# 1-Schematic_CnE_Project_PCB.net
KiCad netlist of a schematic drawn in EasyEDA
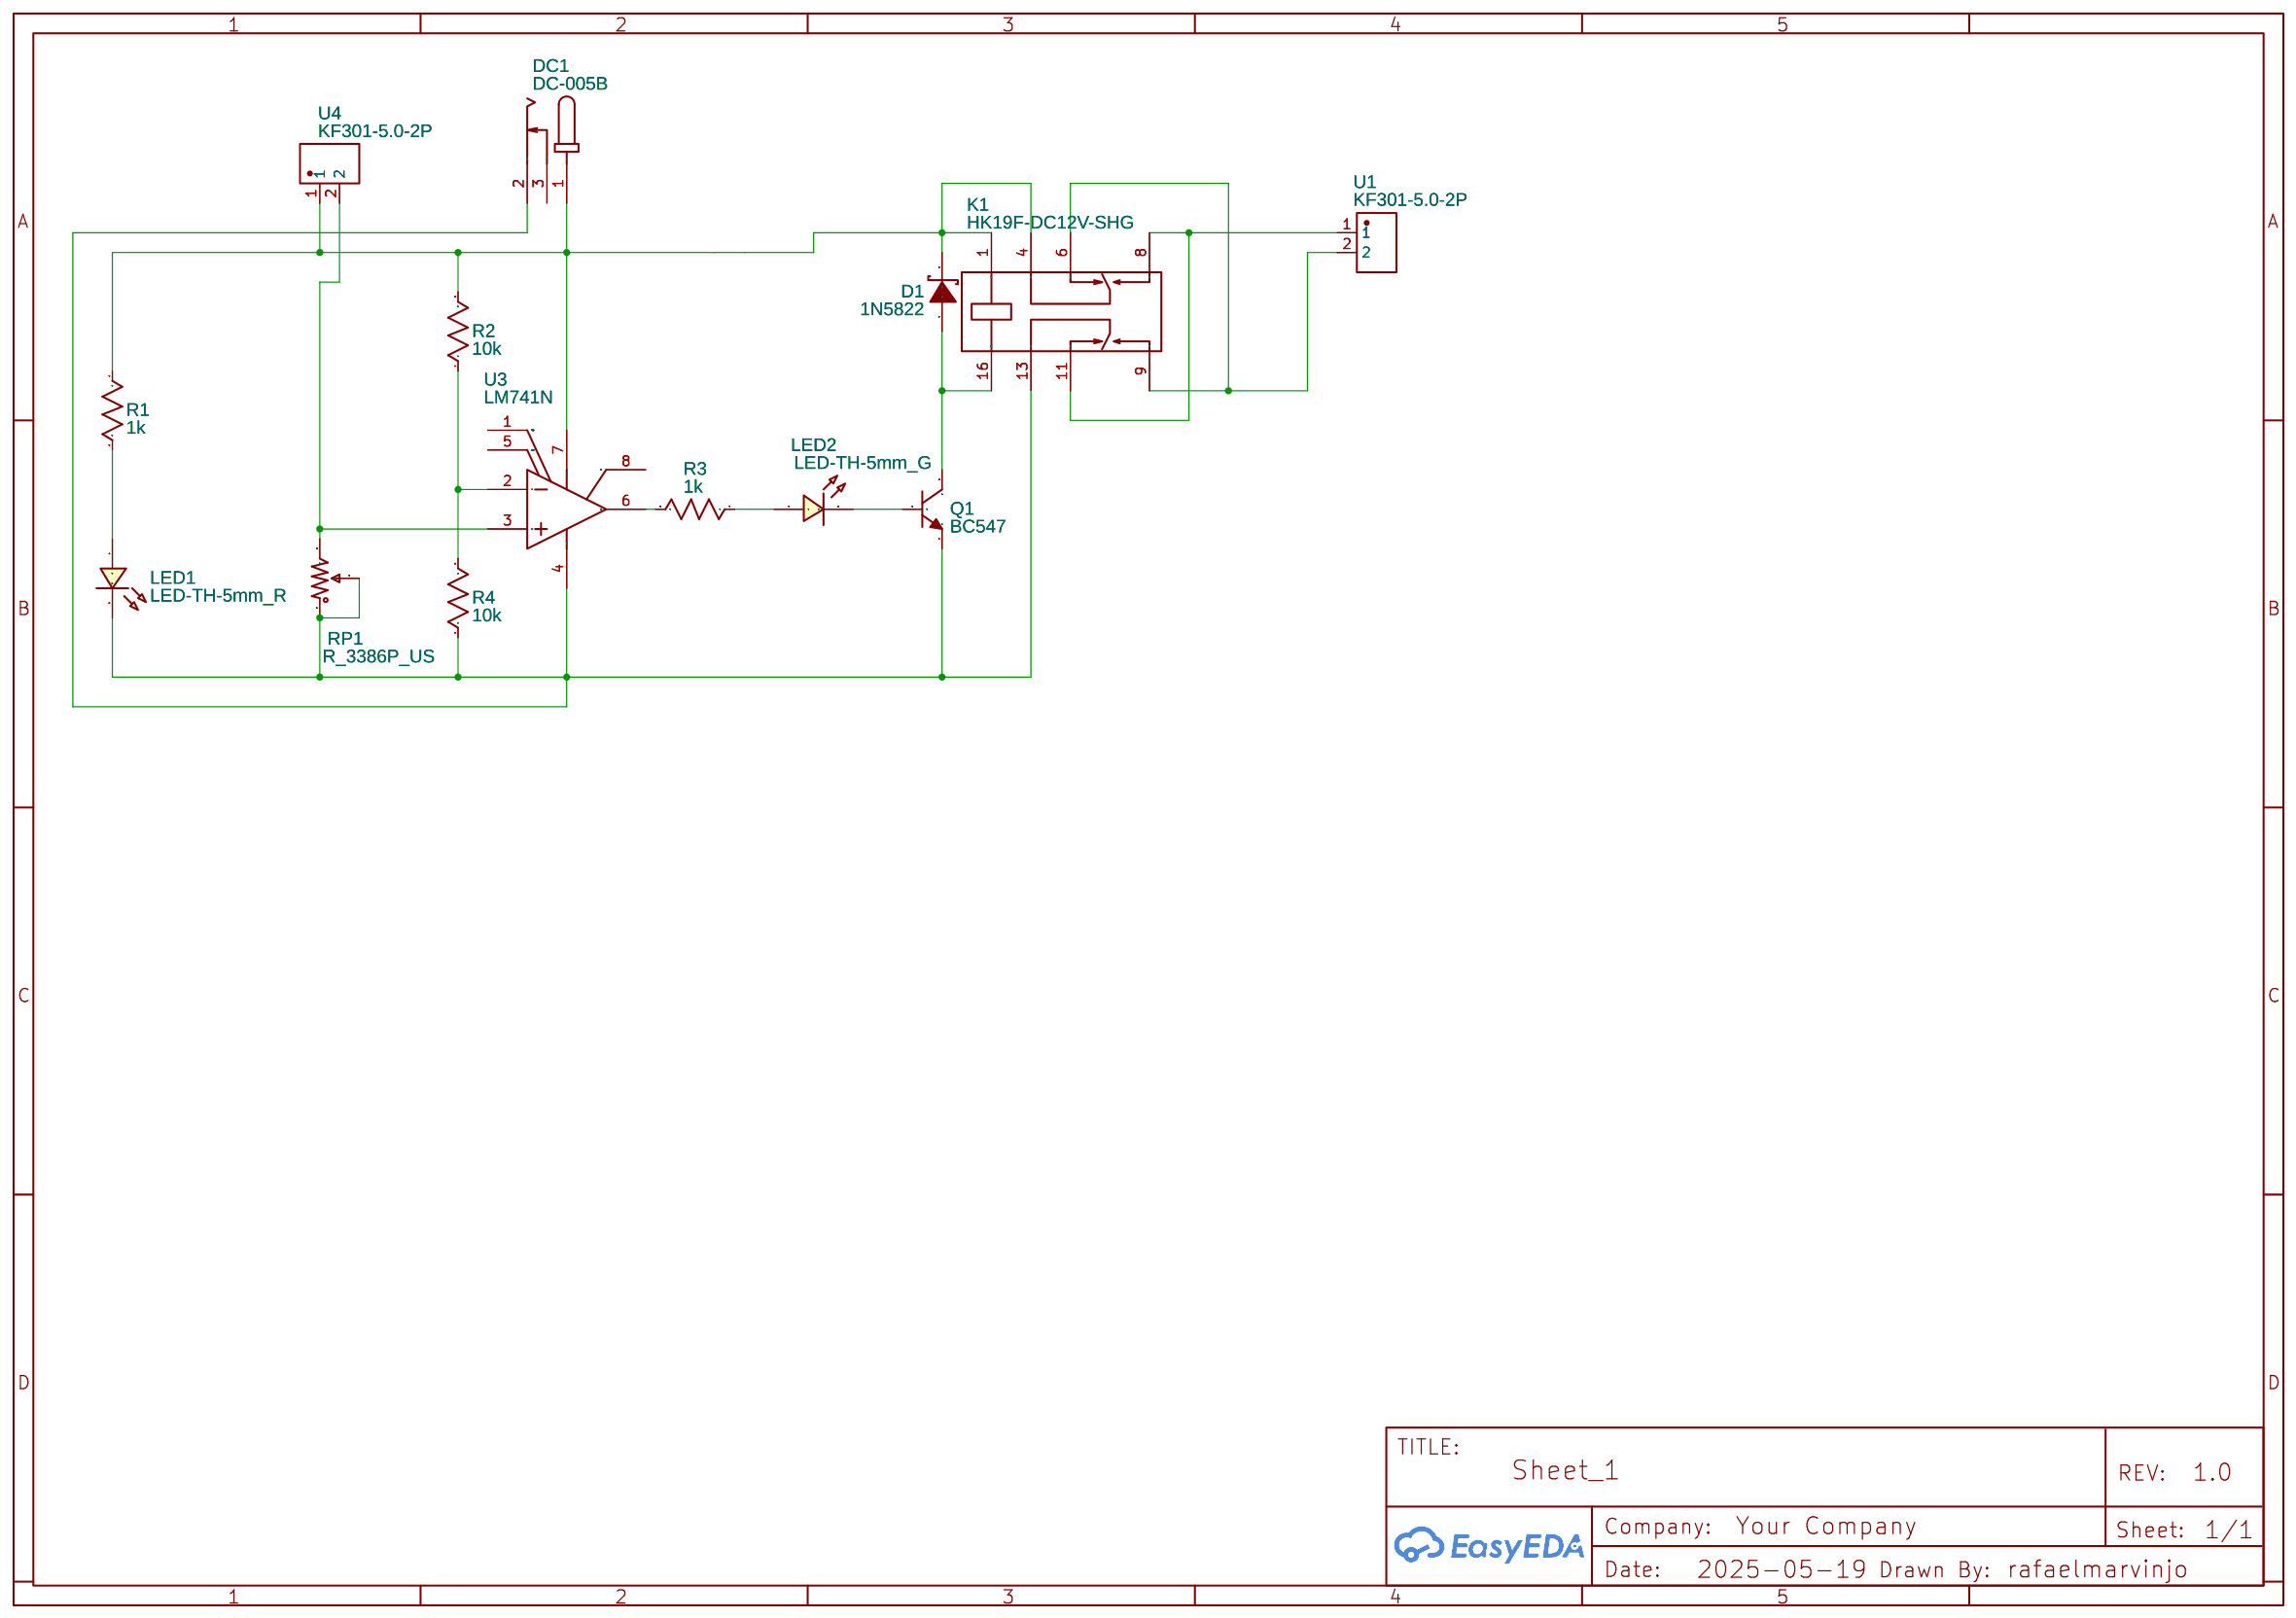
[diagram p0: schematic sheet]

(export (version "E")
  (design (tool "Eeschema 10.0.6"))
  (components
    (comp (ref "D1")
      (value "1N5822")
      (fields (field (name "Manufacturer") "MDD(辰达半导体)"))
      (libsource (lib "") (part "1N5822"))
    )
    (comp (ref "DC1") (value "DC-005B") (libsource (lib "") (part "DC-005B")))
    (comp (ref "K1")
      (value "HK19F-DC12V-SHG")
      (fields (field (name "Manufacturer") "汇科"))
      (libsource (lib "") (part "HK19F-DC12V-SHG"))
    )
    (comp (ref "LED1")
      (value "LED-TH-5mm_R")
      (fields
        (field (name "Manufacturer Part") "333-2SURD/S530-A3")
        (field (name "Manufacturer") "EVERLIGHT(台湾亿光)")
      )
      (libsource (lib "") (part "LED-TH-5mm_R"))
    )
    (comp (ref "LED2")
      (value "LED-TH-5mm_G")
      (fields
        (field (name "Manufacturer Part") "333-2SYGD/S530-E2")
        (field (name "Manufacturer") "EVERLIGHT(台湾亿光)")
      )
      (libsource (lib "") (part "LED-TH-5mm_G"))
    )
    (comp (ref "Q1")
      (value "BC547")
      (fields (field (name "Manufacturer Part") "2N3904") (field (name "Manufacturer") "SEMTECH"))
      (libsource (lib "") (part "2N3904(TO-92)"))
    )
    (comp (ref "R1") (value "1k") (libsource (lib "") (part "R_AXIAL-0.3_US_2")))
    (comp (ref "R2") (value "10k") (libsource (lib "") (part "R_AXIAL-0.3_US_1")))
    (comp (ref "R3") (value "1k") (libsource (lib "") (part "R_AXIAL-0.3_US")))
    (comp (ref "R4") (value "10k") (libsource (lib "") (part "R_AXIAL-0.3_US_1")))
    (comp (ref "RP1") (value "R_3386P_US") (libsource (lib "") (part "R_3386P_US")))
    (comp (ref "U1")
      (value "KF301-5.0-2P")
      (fields (field (name "Manufacturer") "KEFA(科发)"))
      (libsource (lib "") (part "KF301-5.0-2P"))
    )
    (comp (ref "U3")
      (value "LM741N")
      (fields (field (name "Manufacturer") "HGSEMI(华冠)"))
      (libsource (lib "") (part "LM741N"))
    )
    (comp (ref "U4")
      (value "KF301-5.0-2P")
      (fields (field (name "Manufacturer") "KEFA(科发)"))
      (libsource (lib "") (part "KF301-5.0-2P_1"))
    )
  )
  (nets
    (net (code "1") (name "Net-(D1-A)") (class "Default")
      (node (ref "D1") (pin "1") (pinfunction "A_1") (pintype "unspecified"))
      (node (ref "K1") (pin "16") (pinfunction "16_16") (pintype "unspecified"))
      (node (ref "Q1") (pin "3") (pinfunction "C_3") (pintype "unspecified"))
    )
    (net (code "2") (name "Net-(D1-K)") (class "Default")
      (node (ref "D1") (pin "2") (pinfunction "K_2") (pintype "unspecified"))
      (node (ref "DC1") (pin "1") (pinfunction "1_1") (pintype "unspecified"))
      (node (ref "K1") (pin "1") (pinfunction "1_1") (pintype "unspecified"))
      (node (ref "K1") (pin "4") (pinfunction "4_4") (pintype "unspecified"))
      (node (ref "R1") (pin "1") (pinfunction "1_1") (pintype "unspecified"))
      (node (ref "R2") (pin "2") (pinfunction "2_2") (pintype "unspecified"))
      (node (ref "U3") (pin "7") (pinfunction "V+_7") (pintype "passive"))
      (node (ref "U4") (pin "1") (pinfunction "1_1") (pintype "unspecified"))
    )
    (net (code "3") (name "Net-(K1-Pad6)") (class "Default")
      (node (ref "K1") (pin "6") (pinfunction "6_6") (pintype "unspecified"))
      (node (ref "K1") (pin "9") (pinfunction "9_9") (pintype "unspecified"))
      (node (ref "U1") (pin "2") (pinfunction "2_2") (pintype "unspecified"))
    )
    (net (code "4") (name "Net-(K1-Pad11)") (class "Default")
      (node (ref "K1") (pin "11") (pinfunction "11_11") (pintype "unspecified"))
      (node (ref "K1") (pin "8") (pinfunction "8_8") (pintype "unspecified"))
      (node (ref "U1") (pin "1") (pinfunction "1_1") (pintype "unspecified"))
    )
    (net (code "5") (name "Net-(LED1-Pad1)") (class "Default")
      (node (ref "LED1") (pin "1") (pinfunction "1_1") (pintype "unspecified"))
      (node (ref "R1") (pin "2") (pinfunction "2_2") (pintype "unspecified"))
    )
    (net (code "6") (name "Net-(LED2-Pad1)") (class "Default")
      (node (ref "LED2") (pin "1") (pinfunction "1_1") (pintype "unspecified"))
      (node (ref "R3") (pin "1") (pinfunction "1_1") (pintype "unspecified"))
    )
    (net (code "7") (name "Net-(Q1-B)") (class "Default")
      (node (ref "LED2") (pin "2") (pinfunction "2_2") (pintype "unspecified"))
      (node (ref "Q1") (pin "2") (pinfunction "B_2") (pintype "unspecified"))
    )
    (net (code "8") (name "Net-(Q1-E)") (class "Default")
      (node (ref "DC1") (pin "2") (pinfunction "2_2") (pintype "unspecified"))
      (node (ref "K1") (pin "13") (pinfunction "13_13") (pintype "unspecified"))
      (node (ref "LED1") (pin "2") (pinfunction "2_2") (pintype "unspecified"))
      (node (ref "Q1") (pin "1") (pinfunction "E_1") (pintype "unspecified"))
      (node (ref "R4") (pin "1") (pinfunction "1_1") (pintype "unspecified"))
      (node (ref "RP1") (pin "1") (pinfunction "1_1") (pintype "unspecified"))
      (node (ref "RP1") (pin "2") (pinfunction "2_2") (pintype "unspecified"))
      (node (ref "U3") (pin "4") (pinfunction "V-_4") (pintype "passive"))
    )
    (net (code "9") (name "Net-(U3-+IN)") (class "Default")
      (node (ref "RP1") (pin "3") (pinfunction "3_3") (pintype "unspecified"))
      (node (ref "U3") (pin "3") (pinfunction "+IN_3") (pintype "unspecified"))
      (node (ref "U4") (pin "2") (pinfunction "2_2") (pintype "unspecified"))
    )
    (net (code "10") (name "Net-(U3--IN)") (class "Default")
      (node (ref "R2") (pin "1") (pinfunction "1_1") (pintype "unspecified"))
      (node (ref "R4") (pin "2") (pinfunction "2_2") (pintype "unspecified"))
      (node (ref "U3") (pin "2") (pinfunction "-IN_2") (pintype "unspecified"))
    )
    (net (code "11") (name "Net-(U3-OUT)") (class "Default")
      (node (ref "R3") (pin "2") (pinfunction "2_2") (pintype "unspecified"))
      (node (ref "U3") (pin "6") (pinfunction "OUT_6") (pintype "output"))
    )
    (net (code "12") (name "unconnected-(DC1-Pad3)") (class "Default")
      (node (ref "DC1") (pin "3") (pinfunction "3_3") (pintype "unspecified"))
    )
    (net (code "13") (name "unconnected-(U3-NC-Pad8)") (class "Default")
      (node (ref "U3") (pin "8") (pinfunction "NC_8") (pintype "unspecified"))
    )
    (net (code "14") (name "unconnected-(U3-OFFSET_NULL-Pad1)") (class "Default")
      (node (ref "U3") (pin "1") (pinfunction "OFFSET_NULL_1") (pintype "unspecified"))
    )
    (net (code "15") (name "unconnected-(U3-OFFSET_NULL-Pad5)") (class "Default")
      (node (ref "U3") (pin "5") (pinfunction "OFFSET_NULL_5") (pintype "unspecified"))
    )
  )
)
